# Robot_V6.net
KiCad netlist of a schematic drawn in EAGLE
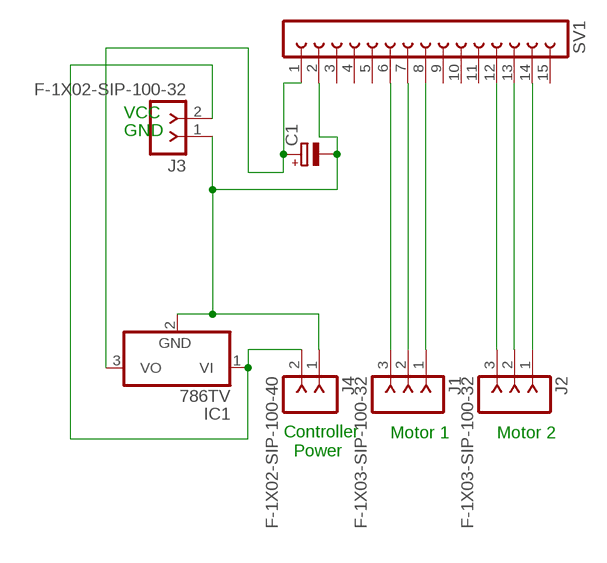
[diagram p0: schematic, sheet 1]

(export (version "E")
  (design (tool "Eeschema 10.0.6"))
  (components
    (comp (ref "C1")
      (value "CPOL-EUE1.8-4")
      (footprint "eagle-import:E1,8-4")
      (libsource (lib "eagle-import") (part "CPOL-EUE1.8-4"))
    )
    (comp (ref "IC1")
      (value "786TV")
      (footprint "eagle-import:TO220V")
      (libsource (lib "eagle-import") (part "78TV6"))
    )
    (comp (ref "J1")
      (value "F-1X03-SIP-100-32")
      (footprint "eagle-import:SIP-100-03-32")
      (libsource (lib "eagle-import") (part "F-1X03-SIP-100-32"))
    )
    (comp (ref "J2")
      (value "F-1X03-SIP-100-32")
      (footprint "eagle-import:SIP-100-03-32")
      (libsource (lib "eagle-import") (part "F-1X03-SIP-100-32"))
    )
    (comp (ref "J3")
      (value "F-1X02-SIP-100-32")
      (footprint "eagle-import:SIP-100-02-32")
      (libsource (lib "eagle-import") (part "F-1X02-SIP-100-32"))
    )
    (comp (ref "J4")
      (value "F-1X02-SIP-100-40")
      (footprint "eagle-import:SIP-100-02-40")
      (libsource (lib "eagle-import") (part "F-1X02-SIP-100-40"))
    )
    (comp (ref "SV1")
      (value "FE15-1")
      (footprint "eagle-import:FE15")
      (libsource (lib "eagle-import") (part "FE15-1"))
    )
  )
  (nets
    (net (code "1") (name "Net-(IC1-GND)") (class "Default")
      (node (ref "C1") (pin "-") (pinfunction "-_-") (pintype "passive"))
      (node (ref "IC1") (pin "2") (pinfunction "GND_2") (pintype "passive"))
      (node (ref "J3") (pin "1") (pinfunction "1_1") (pintype "passive"))
      (node (ref "J4") (pin "1") (pinfunction "1_1") (pintype "passive"))
      (node (ref "SV1") (pin "2") (pinfunction "2_2") (pintype "passive"))
    )
    (net (code "2") (name "Net-(IC1-VI)") (class "Default")
      (node (ref "IC1") (pin "1") (pinfunction "VI_1") (pintype "input"))
      (node (ref "J3") (pin "2") (pinfunction "2_2") (pintype "passive"))
      (node (ref "J4") (pin "2") (pinfunction "2_2") (pintype "passive"))
    )
    (net (code "3") (name "Net-(IC1-VO)") (class "Default")
      (node (ref "C1") (pin "+") (pinfunction "+_+") (pintype "passive"))
      (node (ref "IC1") (pin "3") (pinfunction "VO_3") (pintype "passive"))
      (node (ref "SV1") (pin "1") (pinfunction "1_1") (pintype "passive"))
    )
    (net (code "4") (name "Net-(J1-Pad1)") (class "Default")
      (node (ref "J1") (pin "1") (pinfunction "1_1") (pintype "passive"))
      (node (ref "SV1") (pin "8") (pinfunction "8_8") (pintype "passive"))
    )
    (net (code "5") (name "Net-(J1-Pad2)") (class "Default")
      (node (ref "J1") (pin "2") (pinfunction "2_2") (pintype "passive"))
      (node (ref "SV1") (pin "7") (pinfunction "7_7") (pintype "passive"))
    )
    (net (code "6") (name "Net-(J1-Pad3)") (class "Default")
      (node (ref "J1") (pin "3") (pinfunction "3_3") (pintype "passive"))
      (node (ref "SV1") (pin "6") (pinfunction "6_6") (pintype "passive"))
    )
    (net (code "7") (name "Net-(J2-Pad1)") (class "Default")
      (node (ref "J2") (pin "1") (pinfunction "1_1") (pintype "passive"))
      (node (ref "SV1") (pin "14") (pinfunction "14_14") (pintype "passive"))
    )
    (net (code "8") (name "Net-(J2-Pad2)") (class "Default")
      (node (ref "J2") (pin "2") (pinfunction "2_2") (pintype "passive"))
      (node (ref "SV1") (pin "13") (pinfunction "13_13") (pintype "passive"))
    )
    (net (code "9") (name "Net-(J2-Pad3)") (class "Default")
      (node (ref "J2") (pin "3") (pinfunction "3_3") (pintype "passive"))
      (node (ref "SV1") (pin "12") (pinfunction "12_12") (pintype "passive"))
    )
    (net (code "10") (name "unconnected-(SV1-Pad3)") (class "Default")
      (node (ref "SV1") (pin "3") (pinfunction "3_3") (pintype "passive"))
    )
    (net (code "11") (name "unconnected-(SV1-Pad4)") (class "Default")
      (node (ref "SV1") (pin "4") (pinfunction "4_4") (pintype "passive"))
    )
    (net (code "12") (name "unconnected-(SV1-Pad5)") (class "Default")
      (node (ref "SV1") (pin "5") (pinfunction "5_5") (pintype "passive"))
    )
    (net (code "13") (name "unconnected-(SV1-Pad9)") (class "Default")
      (node (ref "SV1") (pin "9") (pinfunction "9_9") (pintype "passive"))
    )
    (net (code "14") (name "unconnected-(SV1-Pad10)") (class "Default")
      (node (ref "SV1") (pin "10") (pinfunction "10_10") (pintype "passive"))
    )
    (net (code "15") (name "unconnected-(SV1-Pad11)") (class "Default")
      (node (ref "SV1") (pin "11") (pinfunction "11_11") (pintype "passive"))
    )
    (net (code "16") (name "unconnected-(SV1-Pad15)") (class "Default")
      (node (ref "SV1") (pin "15") (pinfunction "15_15") (pintype "passive"))
    )
  )
)
